# PSU5V8A.net
KiCad netlist of a schematic drawn in Altium Designer
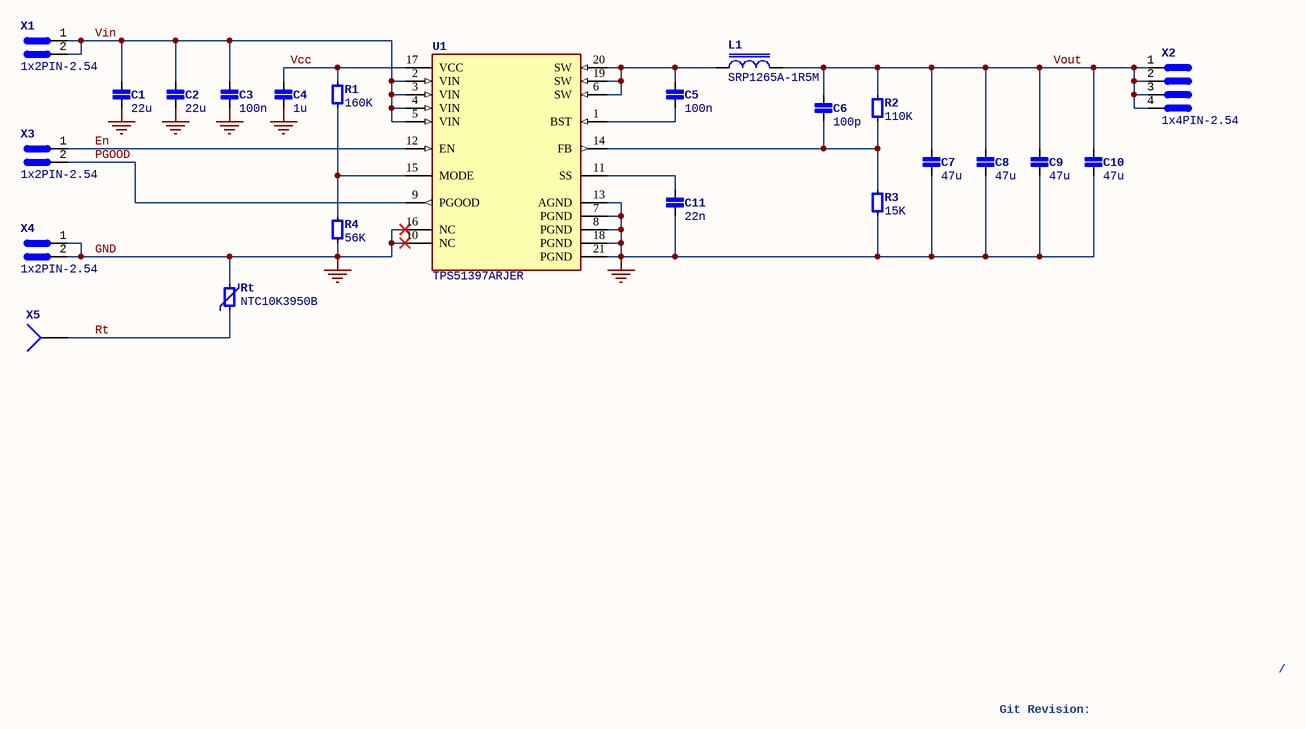
[diagram p0: PSU5V8A.SchDoc]

(export (version "E")
  (design (tool "Eeschema 10.0.6"))
  (components
    (comp (ref "C1") (value "22u") (footprint "CAPC1206N") (libsource (lib "User_leo") (part "CAPACITOR(S)")))
    (comp (ref "C2") (value "22u") (footprint "CAPC1206N") (libsource (lib "User_leo") (part "CAPACITOR(S)")))
    (comp (ref "C3")
      (value "100n")
      (footprint "CAPC0603N")
      (libsource (lib "User_leo") (part "CAPACITOR(S)"))
    )
    (comp (ref "C4") (value "1u") (footprint "CAPC0603N") (libsource (lib "User_leo") (part "CAPACITOR(S)")))
    (comp (ref "C5")
      (value "100n")
      (footprint "CAPC0603N")
      (libsource (lib "User_leo") (part "CAPACITOR(S)"))
    )
    (comp (ref "C6")
      (value "100p")
      (footprint "CAPC0603N")
      (libsource (lib "User_leo") (part "CAPACITOR(S)"))
    )
    (comp (ref "C7") (value "47u") (footprint "CAPC1206N") (libsource (lib "User_leo") (part "CAPACITOR(S)")))
    (comp (ref "C8") (value "47u") (footprint "CAPC1206N") (libsource (lib "User_leo") (part "CAPACITOR(S)")))
    (comp (ref "C9") (value "47u") (footprint "CAPC1206N") (libsource (lib "User_leo") (part "CAPACITOR(S)")))
    (comp (ref "C10")
      (value "47u")
      (footprint "CAPC1206N")
      (libsource (lib "User_leo") (part "CAPACITOR(S)"))
    )
    (comp (ref "C11")
      (value "22n")
      (footprint "CAPC0603N")
      (libsource (lib "User_leo") (part "CAPACITOR(S)"))
    )
    (comp (ref "L1") (value "SRP1265A-1R5M") (footprint "SRR1206M") (libsource (lib "User_leo") (part "IND")))
    (comp (ref "R1")
      (value "160K")
      (footprint "RESC0603N")
      (description "电阻")
      (libsource (lib "User_leo") (part "RESISTOR(S)"))
    )
    (comp (ref "R2")
      (value "110K")
      (footprint "RESC0603N")
      (description "电阻")
      (libsource (lib "User_leo") (part "RESISTOR(S)"))
    )
    (comp (ref "R3")
      (value "15K")
      (footprint "RESC0603N")
      (description "电阻")
      (libsource (lib "User_leo") (part "RESISTOR(S)"))
    )
    (comp (ref "R4")
      (value "56K")
      (footprint "RESC0603N")
      (description "电阻")
      (libsource (lib "User_leo") (part "RESISTOR(S)"))
    )
    (comp (ref "Rt")
      (value "NTC10K3950B")
      (footprint "RESC0603N")
      (description "非线性电阻")
      (libsource (lib "User_leo") (part "PTC"))
    )
    (comp (ref "U1")
      (value "TPS51397ARJER")
      (footprint "FP-RJE0020B-MFG")
      (description "10-A SYNCHRONOUS STEP-DOWN REGUL")
      (libsource (lib "Altium Content Vault") (part "ab47a50a5143bf718f7c4e945efebe0"))
    )
    (comp (ref "X1")
      (value "1x2PIN-2.54")
      (footprint "HDR1X2-P2.54")
      (description "线路板接插件")
      (libsource (lib "User_leo") (part "2PIN-PCB-Connector"))
    )
    (comp (ref "X2")
      (value "1x4PIN-2.54")
      (footprint "HDR2X2-P2.54")
      (description "线路板接插件")
      (libsource (lib "User_leo") (part "4PIN-PCB-Connector"))
    )
    (comp (ref "X3")
      (value "1x2PIN-2.54")
      (footprint "HDR1X2-P2.54")
      (description "线路板接插件")
      (libsource (lib "User_leo") (part "2PIN-PCB-Connector"))
    )
    (comp (ref "X4")
      (value "1x2PIN-2.54")
      (footprint "HDR1X2-P2.54")
      (description "线路板接插件")
      (libsource (lib "User_leo") (part "2PIN-PCB-Connector"))
    )
    (comp (ref "X5")
      (value "Socket")
      (footprint "PIN1")
      (fields (field (name "PUBLISHER") "Altium Limited"))
      (libsource (lib "Miscellaneous Connectors") (part "Socket"))
    )
  )
  (nets
    (net (code "1") (name "/En") (class "Default")
      (node (ref "U1") (pin "12") (pinfunction "EN_12") (pintype "input"))
      (node (ref "X3") (pin "1") (pinfunction "1_1") (pintype "passive"))
    )
    (net (code "2") (name "/PGOOD") (class "Default")
      (node (ref "U1") (pin "9") (pinfunction "PGOOD_9") (pintype "output"))
      (node (ref "X3") (pin "2") (pinfunction "2_2") (pintype "passive"))
    )
    (net (code "3") (name "/Rt") (class "Default")
      (node (ref "Rt") (pin "2") (pinfunction "2_2") (pintype "passive"))
      (node (ref "X5") (pin "1") (pinfunction "1_1") (pintype "passive"))
    )
    (net (code "4") (name "/Vcc") (class "Default")
      (node (ref "C4") (pin "1") (pinfunction "1_1") (pintype "passive"))
      (node (ref "R1") (pin "2") (pinfunction "2_2") (pintype "passive"))
      (node (ref "U1") (pin "17") (pinfunction "VCC_17") (pintype "power_in"))
    )
    (net (code "5") (name "/Vin") (class "Default")
      (node (ref "C1") (pin "1") (pinfunction "1_1") (pintype "passive"))
      (node (ref "C2") (pin "1") (pinfunction "1_1") (pintype "passive"))
      (node (ref "C3") (pin "1") (pinfunction "1_1") (pintype "passive"))
      (node (ref "U1") (pin "2") (pinfunction "VIN_2") (pintype "input"))
      (node (ref "U1") (pin "3") (pinfunction "VIN_3") (pintype "input"))
      (node (ref "U1") (pin "4") (pinfunction "VIN_4") (pintype "input"))
      (node (ref "U1") (pin "5") (pinfunction "VIN_5") (pintype "input"))
      (node (ref "X1") (pin "1") (pinfunction "1_1") (pintype "passive"))
      (node (ref "X1") (pin "2") (pinfunction "2_2") (pintype "passive"))
    )
    (net (code "6") (name "/Vout") (class "Default")
      (node (ref "C10") (pin "1") (pinfunction "1_1") (pintype "passive"))
      (node (ref "C6") (pin "1") (pinfunction "1_1") (pintype "passive"))
      (node (ref "C7") (pin "1") (pinfunction "1_1") (pintype "passive"))
      (node (ref "C8") (pin "1") (pinfunction "1_1") (pintype "passive"))
      (node (ref "C9") (pin "1") (pinfunction "1_1") (pintype "passive"))
      (node (ref "L1") (pin "2") (pinfunction "2_2") (pintype "passive"))
      (node (ref "R2") (pin "1") (pinfunction "1_1") (pintype "passive"))
      (node (ref "X2") (pin "1") (pinfunction "1_1") (pintype "passive"))
      (node (ref "X2") (pin "2") (pinfunction "2_2") (pintype "passive"))
      (node (ref "X2") (pin "3") (pinfunction "3_3") (pintype "passive"))
      (node (ref "X2") (pin "4") (pinfunction "4_4") (pintype "passive"))
    )
    (net (code "7") (name "GND") (class "Default")
      (node (ref "C1") (pin "2") (pinfunction "2_2") (pintype "passive"))
      (node (ref "C10") (pin "2") (pinfunction "2_2") (pintype "passive"))
      (node (ref "C11") (pin "2") (pinfunction "2_2") (pintype "passive"))
      (node (ref "C2") (pin "2") (pinfunction "2_2") (pintype "passive"))
      (node (ref "C3") (pin "2") (pinfunction "2_2") (pintype "passive"))
      (node (ref "C4") (pin "2") (pinfunction "2_2") (pintype "passive"))
      (node (ref "C7") (pin "2") (pinfunction "2_2") (pintype "passive"))
      (node (ref "C8") (pin "2") (pinfunction "2_2") (pintype "passive"))
      (node (ref "C9") (pin "2") (pinfunction "2_2") (pintype "passive"))
      (node (ref "R3") (pin "2") (pinfunction "2_2") (pintype "passive"))
      (node (ref "R4") (pin "1") (pinfunction "1_1") (pintype "passive"))
      (node (ref "Rt") (pin "1") (pinfunction "1_1") (pintype "passive"))
      (node (ref "U1") (pin "10") (pinfunction "NC_10") (pintype "passive"))
      (node (ref "U1") (pin "13") (pinfunction "AGND_13") (pintype "power_in"))
      (node (ref "U1") (pin "16") (pinfunction "NC_16") (pintype "passive"))
      (node (ref "U1") (pin "18") (pinfunction "PGND_18") (pintype "power_in"))
      (node (ref "U1") (pin "21") (pinfunction "PGND_21") (pintype "power_in"))
      (node (ref "U1") (pin "7") (pinfunction "PGND_7") (pintype "power_in"))
      (node (ref "U1") (pin "8") (pinfunction "PGND_8") (pintype "power_in"))
      (node (ref "X4") (pin "1") (pinfunction "1_1") (pintype "passive"))
      (node (ref "X4") (pin "2") (pinfunction "2_2") (pintype "passive"))
    )
    (net (code "8") (name "Net-(C5-Pad1)") (class "Default")
      (node (ref "C5") (pin "1") (pinfunction "1_1") (pintype "passive"))
      (node (ref "L1") (pin "1") (pinfunction "1_1") (pintype "passive"))
      (node (ref "U1") (pin "19") (pinfunction "SW_19") (pintype "input"))
      (node (ref "U1") (pin "20") (pinfunction "SW_20") (pintype "input"))
      (node (ref "U1") (pin "6") (pinfunction "SW_6") (pintype "input"))
    )
    (net (code "9") (name "Net-(U1-BST)") (class "Default")
      (node (ref "C5") (pin "2") (pinfunction "2_2") (pintype "passive"))
      (node (ref "U1") (pin "1") (pinfunction "BST_1") (pintype "input"))
    )
    (net (code "10") (name "Net-(U1-FB)") (class "Default")
      (node (ref "C6") (pin "2") (pinfunction "2_2") (pintype "passive"))
      (node (ref "R2") (pin "2") (pinfunction "2_2") (pintype "passive"))
      (node (ref "R3") (pin "1") (pinfunction "1_1") (pintype "passive"))
      (node (ref "U1") (pin "14") (pinfunction "FB_14") (pintype "output"))
    )
    (net (code "11") (name "Net-(U1-MODE)") (class "Default")
      (node (ref "R1") (pin "1") (pinfunction "1_1") (pintype "passive"))
      (node (ref "R4") (pin "2") (pinfunction "2_2") (pintype "passive"))
      (node (ref "U1") (pin "15") (pinfunction "MODE_15") (pintype "passive"))
    )
    (net (code "12") (name "Net-(U1-SS)") (class "Default")
      (node (ref "C11") (pin "1") (pinfunction "1_1") (pintype "passive"))
      (node (ref "U1") (pin "11") (pinfunction "SS_11") (pintype "passive"))
    )
  )
)
